# PWR_N2V5A.net
KiCad netlist of a schematic drawn in Altium Designer
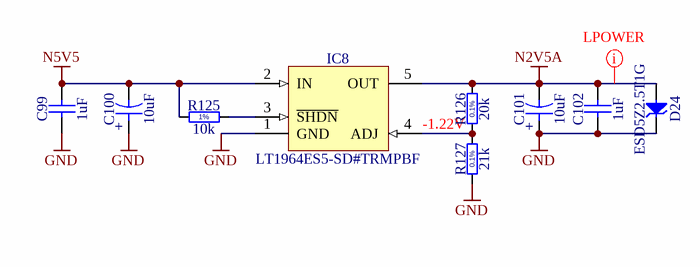
[diagram p0: PWR_N2V5A.SchDoc]

(export (version "E")
  (design (tool "Eeschema 10.0.6"))
  (components
    (comp (ref "C99")
      (value "1uF")
      (footprint "CAPC1005X55N")
      (description "Non-polarised capacitor")
      (fields
        (field (name "PART NUMBER") "CC0402_1UF_16V_10%_X5R")
        (field (name "VOLTAGE") "16V")
        (field (name "AUTHOR") "CERN DEM JLC")
      )
      (libsource (lib "Capacitors") (part "Capacitor - non polarized"))
    )
    (comp (ref "C100")
      (value "10uF")
      (footprint "CAPMP3216X180N")
      (description "Polarised capacitor")
      (fields
        (field (name "PART NUMBER") "CTE3216-18_10UF_16V_20%_AVX_TCJ")
        (field (name "VOLTAGE") "16V")
        (field (name "AUTHOR") "CERN DEM JLC")
      )
      (libsource (lib "Capacitors") (part "Capacitor - polarized"))
    )
    (comp (ref "C101")
      (value "10uF")
      (footprint "CAPMP3216X180N")
      (description "Polarised capacitor")
      (fields
        (field (name "PART NUMBER") "CTE3216-18_10UF_16V_20%_AVX_TCJ")
        (field (name "VOLTAGE") "16V")
        (field (name "AUTHOR") "CERN DEM JLC")
      )
      (libsource (lib "Capacitors") (part "Capacitor - polarized"))
    )
    (comp (ref "C102")
      (value "1uF")
      (footprint "CAPC1005X55N")
      (description "Non-polarised capacitor")
      (fields
        (field (name "PART NUMBER") "CC0402_1UF_16V_10%_X5R")
        (field (name "VOLTAGE") "16V")
        (field (name "AUTHOR") "CERN DEM JLC")
      )
      (libsource (lib "Capacitors") (part "Capacitor - non polarized"))
    )
    (comp (ref "D24")
      (value "ESD5Z2.5T1G")
      (footprint "SODFL1608X70N")
      (description "Zener Diode")
      (fields
        (field (name "VOLTAGE") "2.5V")
        (field (name "POWER") "500mW")
        (field (name "AUTHOR") "CERN DEM JLC")
      )
      (libsource (lib "ICs And Semiconductors") (part "Diode Zener"))
    )
    (comp (ref "IC8")
      (value "LT1964ES5-SD#TRMPBF")
      (footprint "SOT95P280X100-5N")
      (description "200mA, Low Noise, Low Dropout Negative Micropower Regulator")
      (fields (field (name "MANUFACTURER") "LINEAR TECHNOLOGY") (field (name "AUTHOR") "CERN DEM JLC"))
      (libsource (lib "ICs And Semiconductors") (part "LT1964-SD"))
    )
    (comp (ref "R125")
      (value "10k")
      (footprint "RESC1005X40N")
      (description "Resistor - 1%")
      (fields
        (field (name "PART NUMBER") "R0402_10K_1%_0.0625W_100PPM")
        (field (name "MANUFACTURER") "GENERIC")
        (field (name "AUTHOR") "CERN DEM JLC")
      )
      (libsource (lib "Resistors") (part "Resistor - 1%"))
    )
    (comp (ref "R126")
      (value "20k")
      (footprint "RESC1608X55N")
      (description "Resistor - 0.1%")
      (fields
        (field (name "PART NUMBER") "R0603_20K_0.1%_0.063W_10PPM")
        (field (name "POWER") "0.063W")
        (field (name "AUTHOR") "CERN DEM JLC")
      )
      (libsource (lib "Resistors") (part "Resistor - 0.1%"))
    )
    (comp (ref "R127")
      (value "21k")
      (footprint "RESC1608X55N")
      (description "Resistor - 0.1%")
      (fields
        (field (name "PART NUMBER") "R0603_21K_0.1%_0.063W_10PPM")
        (field (name "POWER") "0.063W")
        (field (name "AUTHOR") "CERN DEM JLC")
      )
      (libsource (lib "Resistors") (part "Resistor - 0.1%"))
    )
  )
  (nets
    (net (code "1") (name "GND") (class "Default")
      (node (ref "C100") (pin "1") (pinfunction "1_1") (pintype "passive"))
      (node (ref "C101") (pin "1") (pinfunction "1_1") (pintype "passive"))
      (node (ref "C102") (pin "1") (pinfunction "1_1") (pintype "passive"))
      (node (ref "C99") (pin "1") (pinfunction "1_1") (pintype "passive"))
      (node (ref "D24") (pin "1") (pinfunction "C_1") (pintype "passive"))
      (node (ref "IC8") (pin "1") (pinfunction "GND_1") (pintype "power_in"))
      (node (ref "R127") (pin "1") (pinfunction "1_1") (pintype "passive"))
    )
    (net (code "2") (name "N2V5A") (class "Default")
      (node (ref "C101") (pin "2") (pinfunction "2_2") (pintype "passive"))
      (node (ref "C102") (pin "2") (pinfunction "2_2") (pintype "passive"))
      (node (ref "D24") (pin "2") (pinfunction "A_2") (pintype "passive"))
      (node (ref "IC8") (pin "5") (pinfunction "OUT_5") (pintype "power_in"))
      (node (ref "R126") (pin "2") (pinfunction "2_2") (pintype "passive"))
    )
    (net (code "3") (name "N5V5") (class "Default")
      (node (ref "C100") (pin "2") (pinfunction "2_2") (pintype "passive"))
      (node (ref "C99") (pin "2") (pinfunction "2_2") (pintype "passive"))
      (node (ref "IC8") (pin "2") (pinfunction "IN_2") (pintype "input"))
      (node (ref "R125") (pin "1") (pinfunction "1_1") (pintype "passive"))
    )
    (net (code "4") (name "Net-(IC8-ADJ)") (class "Default")
      (node (ref "IC8") (pin "4") (pinfunction "ADJ_4") (pintype "input"))
      (node (ref "R126") (pin "1") (pinfunction "1_1") (pintype "passive"))
      (node (ref "R127") (pin "2") (pinfunction "2_2") (pintype "passive"))
    )
    (net (code "5") (name "Net-(IC8-~{SHDN})") (class "Default")
      (node (ref "IC8") (pin "3") (pinfunction "~{SHDN}_3") (pintype "input"))
      (node (ref "R125") (pin "2") (pinfunction "2_2") (pintype "passive"))
    )
  )
)
